# Power_Sheet.net
KiCad netlist of a schematic drawn in Altium Designer
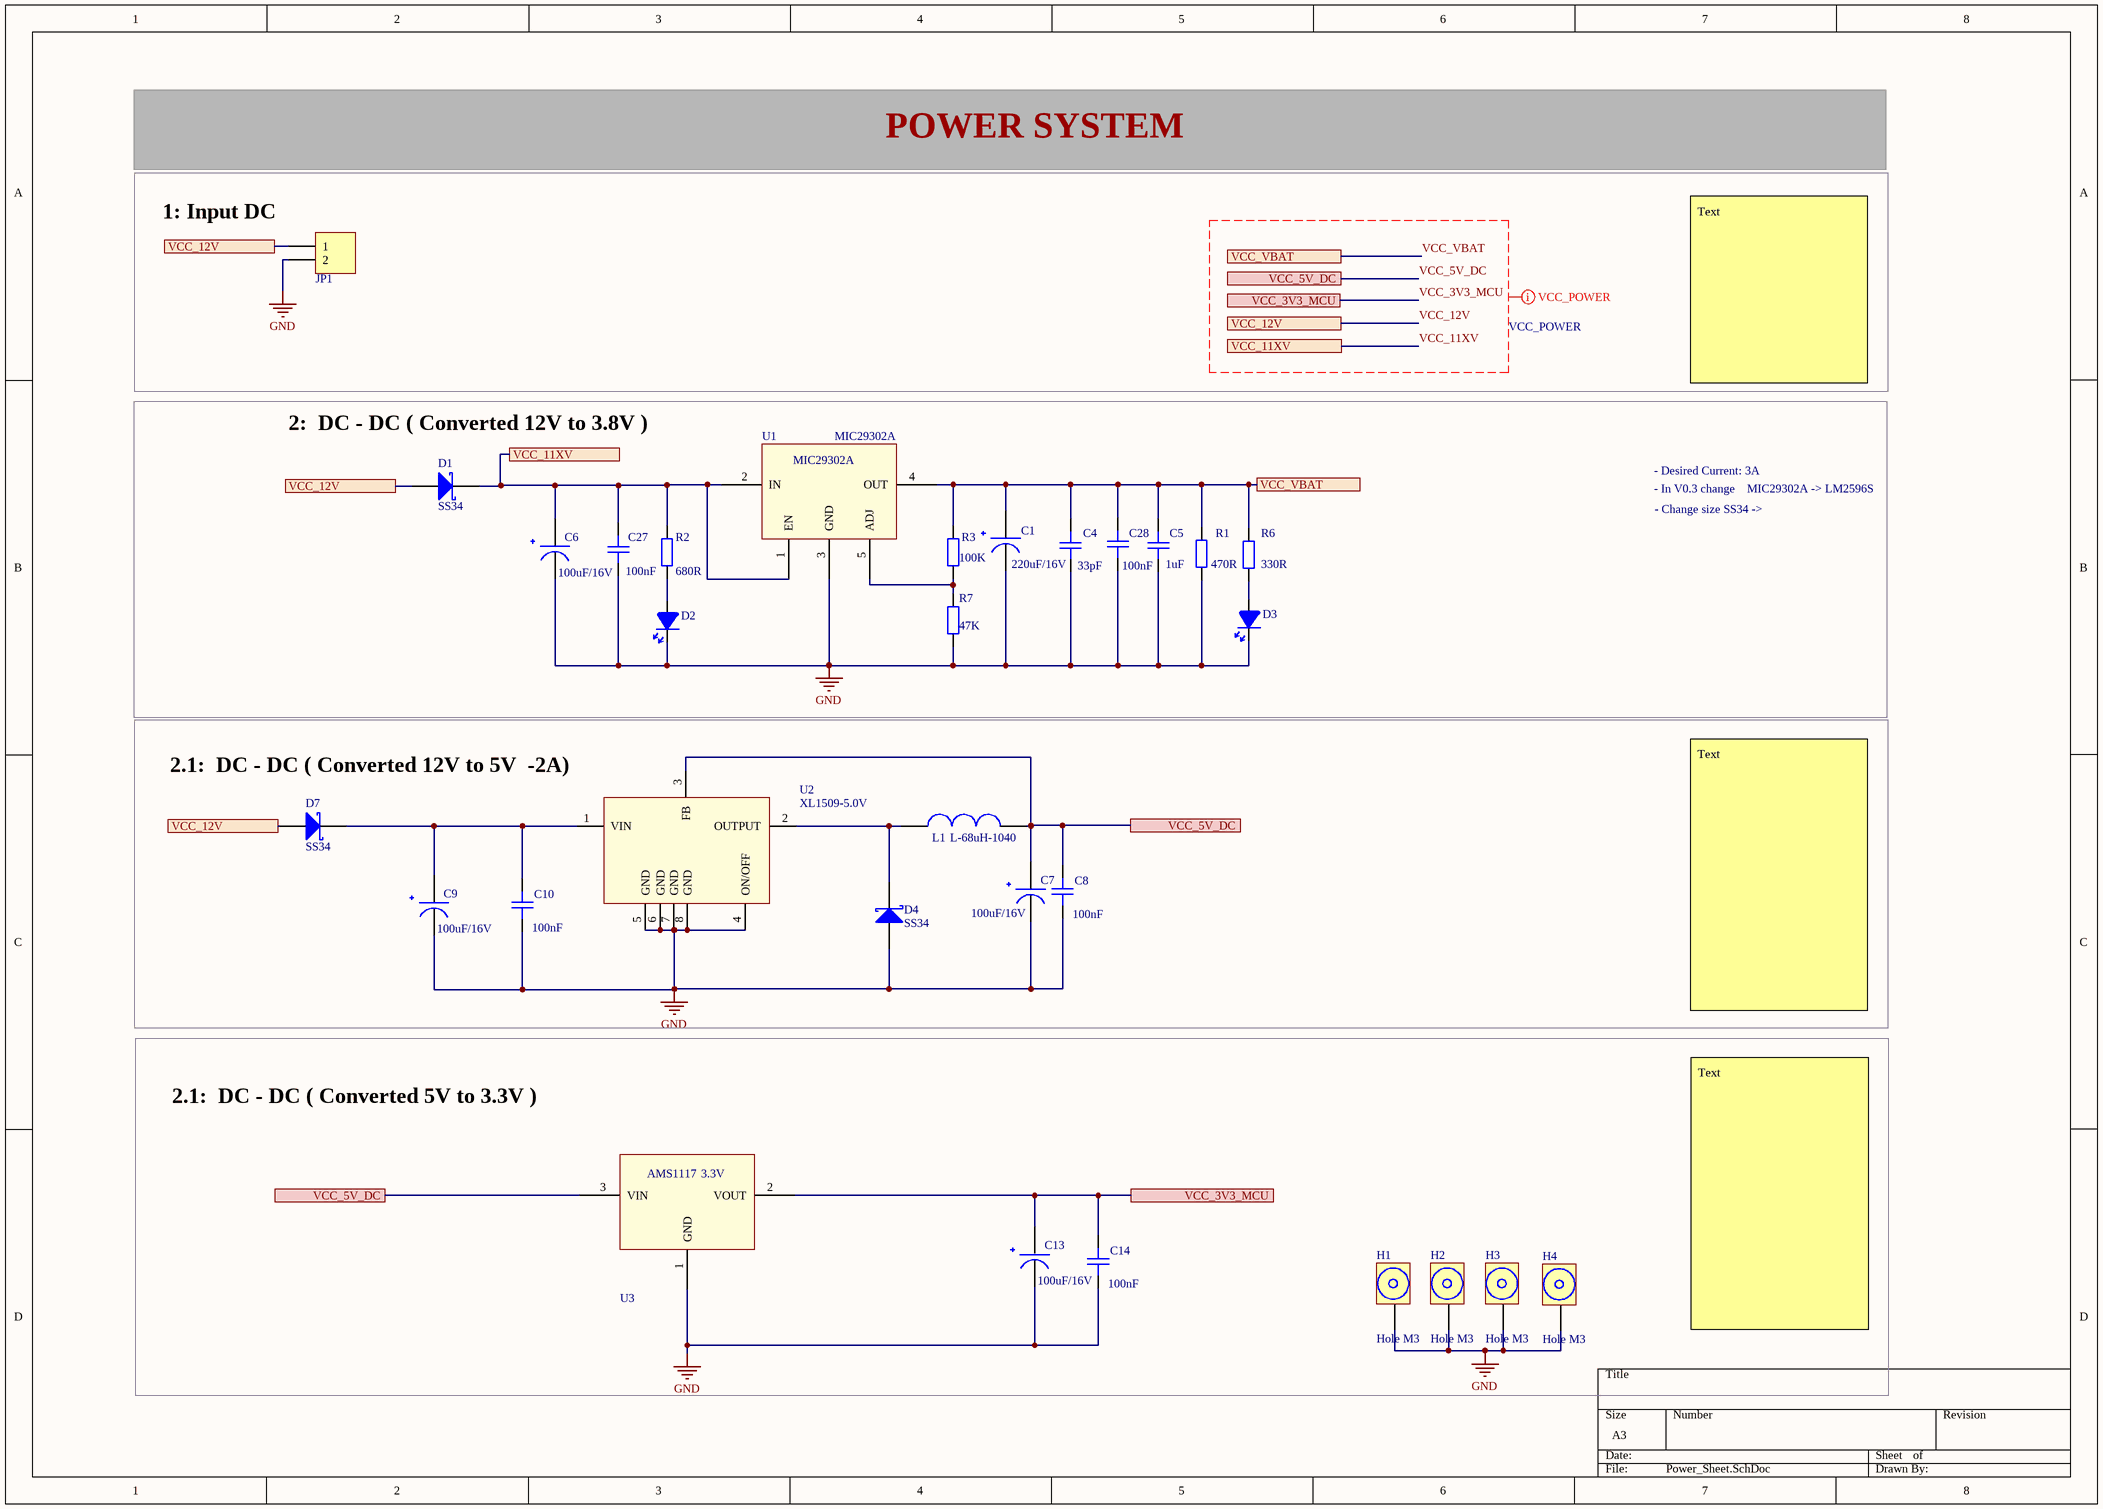
[diagram p0: Power_Sheet.SchDoc]

(export (version "E")
  (design (tool "Eeschema 10.0.6"))
  (components
    (comp (ref "C1")
      (value "220uF/16V")
      (footprint "CAPACITOR 6.3x7.7mm")
      (description "Capacitor 220uF - 16V. Size 6.3x7,7mm")
      (libsource (lib "FM_Components") (part "CAP 220uF"))
    )
    (comp (ref "C4")
      (value "33pF")
      (footprint "CAPC-0603 (1608)")
      (description "CAP SMD, Not Fill, 0603")
      (libsource (lib "BYTECH_HW_LIB_2019") (part "CAPC NF 0603"))
    )
    (comp (ref "C5")
      (value "1uF")
      (footprint "CAPC-0603 (1608)")
      (description "CAP SMD, Not Fill, 0603")
      (libsource (lib "BYTECH_HW_LIB_2019") (part "CAPC NF 0603"))
    )
    (comp (ref "C6")
      (value "100uF/16V")
      (footprint "CAP 6.3MMx5.4MM")
      (description "Capacitor 100uF - 16V. Size 6.3x5.4mm")
      (libsource (lib "FM_Components") (part "CAP 100uF"))
    )
    (comp (ref "C7")
      (value "100uF/16V")
      (footprint "CAP 6.3MMx5.4MM")
      (description "Capacitor 100uF - 16V. Size 6.3x5.4mm")
      (libsource (lib "FM_Components") (part "CAP 100uF"))
    )
    (comp (ref "C8")
      (value "100nF")
      (footprint "CAPC-0603 (1608)")
      (description "CAP SMD, Not Fill, 0603")
      (libsource (lib "BYTECH_HW_LIB_2019") (part "CAPC NF 0603"))
    )
    (comp (ref "C9")
      (value "100uF/16V")
      (footprint "CAP 6.3MMx5.4MM")
      (description "Capacitor 100uF - 16V. Size 6.3x5.4mm")
      (libsource (lib "FM_Components") (part "CAP 100uF"))
    )
    (comp (ref "C10")
      (value "100nF")
      (footprint "CAPC-0603 (1608)")
      (description "CAP SMD, Not Fill, 0603")
      (libsource (lib "BYTECH_HW_LIB_2019") (part "CAPC NF 0603"))
    )
    (comp (ref "C13")
      (value "100uF/16V")
      (footprint "CAP 6.3MMx5.4MM")
      (description "Capacitor 100uF - 16V. Size 6.3x5.4mm")
      (libsource (lib "FM_Components") (part "CAP 100uF"))
    )
    (comp (ref "C14")
      (value "100nF")
      (footprint "CAPC-0603 (1608)")
      (description "CAP SMD, Not Fill, 0603")
      (libsource (lib "BYTECH_HW_LIB_2019") (part "CAPC NF 0603"))
    )
    (comp (ref "C27")
      (value "100nF")
      (footprint "CAPC-0603 (1608)")
      (description "CAP SMD, Not Fill, 0603")
      (libsource (lib "BYTECH_HW_LIB_2019") (part "CAPC NF 0603"))
    )
    (comp (ref "C28")
      (value "100nF")
      (footprint "CAPC-0603 (1608)")
      (description "CAP SMD, Not Fill, 0603")
      (libsource (lib "BYTECH_HW_LIB_2019") (part "CAPC NF 0603"))
    )
    (comp (ref "D1")
      (value "SS34")
      (footprint "DIODE_DO214AC_SMA")
      (description "DIODE SCHOTTKY 40V 3A SMA")
      (libsource (lib "BYTECH_HW_LIB_2019") (part "SS34"))
    )
    (comp (ref "D2")
      (value "LED_0805_PW")
      (footprint "LED_0805_PW")
      (libsource (lib "FM_Components") (part "LED_0805_PW"))
    )
    (comp (ref "D3")
      (value "LED_0805_PW")
      (footprint "LED_0805_PW")
      (libsource (lib "FM_Components") (part "LED_0805_PW"))
    )
    (comp (ref "D4")
      (value "SS34")
      (footprint "DIODE_DO214AC_SMA")
      (description "DIODE SCHOTTKY 40V 3A SMA")
      (libsource (lib "BYTECH_HW_LIB_2019") (part "SS34"))
    )
    (comp (ref "D7")
      (value "SS34")
      (footprint "DIODE_DO214AC_SMA")
      (description "DIODE SCHOTTKY 40V 3A SMA")
      (libsource (lib "BYTECH_HW_LIB_2019") (part "SS34"))
    )
    (comp (ref "H1")
      (value "Hole M3")
      (footprint "Hole Size 3M")
      (libsource (lib "FM_Components") (part "Hole M3"))
    )
    (comp (ref "H2")
      (value "Hole M3")
      (footprint "Hole Size 3M")
      (libsource (lib "FM_Components") (part "Hole M3"))
    )
    (comp (ref "H3")
      (value "Hole M3")
      (footprint "Hole Size 3M")
      (libsource (lib "FM_Components") (part "Hole M3"))
    )
    (comp (ref "H4")
      (value "Hole M3")
      (footprint "Hole Size 3M")
      (libsource (lib "FM_Components") (part "Hole M3"))
    )
    (comp (ref "JP1")
      (value "Header 2_1")
      (footprint "HED2")
      (description "Header, 2-Pin")
      (fields (field (name "MANUFACTURER") "Generic Components"))
      (libsource (lib "syhaunguyen") (part "Header 2_1"))
    )
    (comp (ref "L1")
      (value "L-68uH-1040")
      (footprint "68uH - 2A - 1040")
      (libsource (lib "FM_Components") (part "L-68uH-1040"))
    )
    (comp (ref "R1")
      (value "470R")
      (footprint "RESC-0603 (1608)")
      (description "RES SMD 5.1 OHM 1% 1/10W 0603")
      (fields (field (name "MPN") "CRCW06035R10FKEA") (field (name "MFR") "Vishay Dale"))
      (libsource (lib "BYTECH_HW_LIB_2019") (part "CRCW06035R10FKEA"))
    )
    (comp (ref "R2")
      (value "680R")
      (footprint "RESC-0603 (1608)")
      (description "RES SMD 5.1 OHM 1% 1/10W 0603")
      (fields (field (name "MPN") "CRCW06035R10FKEA") (field (name "MFR") "Vishay Dale"))
      (libsource (lib "BYTECH_HW_LIB_2019") (part "CRCW06035R10FKEA"))
    )
    (comp (ref "R3")
      (value "100K")
      (footprint "RESC-0603 (1608)")
      (description "RES SMD 5.1 OHM 1% 1/10W 0603")
      (fields (field (name "MPN") "CRCW06035R10FKEA") (field (name "MFR") "Vishay Dale"))
      (libsource (lib "") (part "CRCW06035R10FKEA_1"))
    )
    (comp (ref "R6")
      (value "330R")
      (footprint "RESC-0603 (1608)")
      (description "RES SMD 5.1 OHM 1% 1/10W 0603")
      (fields (field (name "MPN") "CRCW06035R10FKEA") (field (name "MFR") "Vishay Dale"))
      (libsource (lib "BYTECH_HW_LIB_2019") (part "CRCW06035R10FKEA"))
    )
    (comp (ref "R7")
      (value "47K")
      (footprint "RESC-0603 (1608)")
      (description "RES SMD 5.1 OHM 1% 1/10W 0603")
      (fields (field (name "MPN") "CRCW06035R10FKEA") (field (name "MFR") "Vishay Dale"))
      (libsource (lib "BYTECH_HW_LIB_2019") (part "CRCW06035R10FKEA"))
    )
    (comp (ref "U1")
      (value "MIC29302A")
      (footprint "MIC29302A")
      (libsource (lib "FM_Components") (part "MIC29302A"))
    )
    (comp (ref "U2")
      (value "XL1509-5.0V")
      (footprint "XL1509-5V")
      (description "XL1509-5V FROM XLSEMI")
      (libsource (lib "FM_Components") (part "XL1509-5V"))
    )
    (comp (ref "U3")
      (value "AMS1117 - 3.3V")
      (footprint "AMS1117 -3.3V")
      (libsource (lib "FM_Components") (part "AMS1117 - 3.3V"))
    )
  )
  (nets
    (net (code "1") (name "/VCC_3V3_MCU") (class "Default")
      (node (ref "C13") (pin "1") (pinfunction "1_1") (pintype "passive"))
      (node (ref "C14") (pin "2") (pinfunction "2_2") (pintype "passive"))
      (node (ref "U3") (pin "2") (pinfunction "VOUT_2") (pintype "passive"))
    )
    (net (code "2") (name "/VCC_5V_DC") (class "Default")
      (node (ref "C7") (pin "1") (pinfunction "1_1") (pintype "passive"))
      (node (ref "C8") (pin "2") (pinfunction "2_2") (pintype "passive"))
      (node (ref "L1") (pin "2") (pinfunction "2_2") (pintype "passive"))
      (node (ref "U2") (pin "3") (pinfunction "FB_3") (pintype "passive"))
      (node (ref "U3") (pin "3") (pinfunction "VIN_3") (pintype "passive"))
    )
    (net (code "3") (name "/VCC_11XV") (class "Default")
      (node (ref "C27") (pin "2") (pinfunction "2_2") (pintype "passive"))
      (node (ref "C6") (pin "1") (pinfunction "1_1") (pintype "passive"))
      (node (ref "D1") (pin "2") (pinfunction "K_2") (pintype "passive"))
      (node (ref "R2") (pin "2") (pinfunction "2_2") (pintype "passive"))
      (node (ref "U1") (pin "1") (pinfunction "EN_1") (pintype "passive"))
      (node (ref "U1") (pin "2") (pinfunction "IN_2") (pintype "passive"))
    )
    (net (code "4") (name "/VCC_12V") (class "Default")
      (node (ref "D1") (pin "1") (pinfunction "A_1") (pintype "passive"))
      (node (ref "D7") (pin "1") (pinfunction "A_1") (pintype "passive"))
      (node (ref "JP1") (pin "1") (pinfunction "1_1") (pintype "passive"))
    )
    (net (code "5") (name "/VCC_VBAT") (class "Default")
      (node (ref "C1") (pin "1") (pinfunction "1_1") (pintype "passive"))
      (node (ref "C28") (pin "2") (pinfunction "2_2") (pintype "passive"))
      (node (ref "C4") (pin "2") (pinfunction "2_2") (pintype "passive"))
      (node (ref "C5") (pin "2") (pinfunction "2_2") (pintype "passive"))
      (node (ref "R1") (pin "2") (pinfunction "2_2") (pintype "passive"))
      (node (ref "R3") (pin "1") (pinfunction "1_1") (pintype "passive"))
      (node (ref "R6") (pin "2") (pinfunction "2_2") (pintype "passive"))
      (node (ref "U1") (pin "4") (pinfunction "OUT_4") (pintype "passive"))
    )
    (net (code "6") (name "GND") (class "Default")
      (node (ref "C1") (pin "2") (pinfunction "2_2") (pintype "passive"))
      (node (ref "C10") (pin "1") (pinfunction "1_1") (pintype "passive"))
      (node (ref "C13") (pin "2") (pinfunction "2_2") (pintype "passive"))
      (node (ref "C14") (pin "1") (pinfunction "1_1") (pintype "passive"))
      (node (ref "C27") (pin "1") (pinfunction "1_1") (pintype "passive"))
      (node (ref "C28") (pin "1") (pinfunction "1_1") (pintype "passive"))
      (node (ref "C4") (pin "1") (pinfunction "1_1") (pintype "passive"))
      (node (ref "C5") (pin "1") (pinfunction "1_1") (pintype "passive"))
      (node (ref "C6") (pin "2") (pinfunction "2_2") (pintype "passive"))
      (node (ref "C7") (pin "2") (pinfunction "2_2") (pintype "passive"))
      (node (ref "C8") (pin "1") (pinfunction "1_1") (pintype "passive"))
      (node (ref "C9") (pin "2") (pinfunction "2_2") (pintype "passive"))
      (node (ref "D2") (pin "2") (pinfunction "K_2") (pintype "passive"))
      (node (ref "D3") (pin "2") (pinfunction "K_2") (pintype "passive"))
      (node (ref "D4") (pin "1") (pinfunction "A_1") (pintype "passive"))
      (node (ref "H1") (pin "1") (pinfunction "GND_1") (pintype "passive"))
      (node (ref "H2") (pin "1") (pinfunction "GND_1") (pintype "passive"))
      (node (ref "H3") (pin "1") (pinfunction "GND_1") (pintype "passive"))
      (node (ref "H4") (pin "1") (pinfunction "GND_1") (pintype "passive"))
      (node (ref "JP1") (pin "2") (pinfunction "2_2") (pintype "passive"))
      (node (ref "R1") (pin "1") (pinfunction "1_1") (pintype "passive"))
      (node (ref "R7") (pin "1") (pinfunction "1_1") (pintype "passive"))
      (node (ref "U1") (pin "3") (pinfunction "GND_3") (pintype "passive"))
      (node (ref "U2") (pin "4") (pinfunction "ON/OFF_4") (pintype "passive"))
      (node (ref "U2") (pin "5") (pinfunction "GND_5") (pintype "passive"))
      (node (ref "U2") (pin "6") (pinfunction "GND_6") (pintype "passive"))
      (node (ref "U2") (pin "7") (pinfunction "GND_7") (pintype "passive"))
      (node (ref "U2") (pin "8") (pinfunction "GND_8") (pintype "passive"))
      (node (ref "U3") (pin "1") (pinfunction "GND_1") (pintype "passive"))
    )
    (net (code "7") (name "Net-(D2-A)") (class "Default")
      (node (ref "D2") (pin "1") (pinfunction "A_1") (pintype "passive"))
      (node (ref "R2") (pin "1") (pinfunction "1_1") (pintype "passive"))
    )
    (net (code "8") (name "Net-(D3-A)") (class "Default")
      (node (ref "D3") (pin "1") (pinfunction "A_1") (pintype "passive"))
      (node (ref "R6") (pin "1") (pinfunction "1_1") (pintype "passive"))
    )
    (net (code "9") (name "Net-(D4-K)") (class "Default")
      (node (ref "D4") (pin "2") (pinfunction "K_2") (pintype "passive"))
      (node (ref "L1") (pin "1") (pinfunction "331_1") (pintype "passive"))
      (node (ref "U2") (pin "2") (pinfunction "OUTPUT_2") (pintype "passive"))
    )
    (net (code "10") (name "Net-(D7-K)") (class "Default")
      (node (ref "C10") (pin "2") (pinfunction "2_2") (pintype "passive"))
      (node (ref "C9") (pin "1") (pinfunction "1_1") (pintype "passive"))
      (node (ref "D7") (pin "2") (pinfunction "K_2") (pintype "passive"))
      (node (ref "U2") (pin "1") (pinfunction "VIN_1") (pintype "passive"))
    )
    (net (code "11") (name "Net-(U1-ADJ)") (class "Default")
      (node (ref "R3") (pin "2") (pinfunction "2_2") (pintype "passive"))
      (node (ref "R7") (pin "2") (pinfunction "2_2") (pintype "passive"))
      (node (ref "U1") (pin "5") (pinfunction "ADJ_5") (pintype "passive"))
    )
  )
)
